# 18500_pack_v2.net
KiCad netlist of a schematic drawn in EAGLE
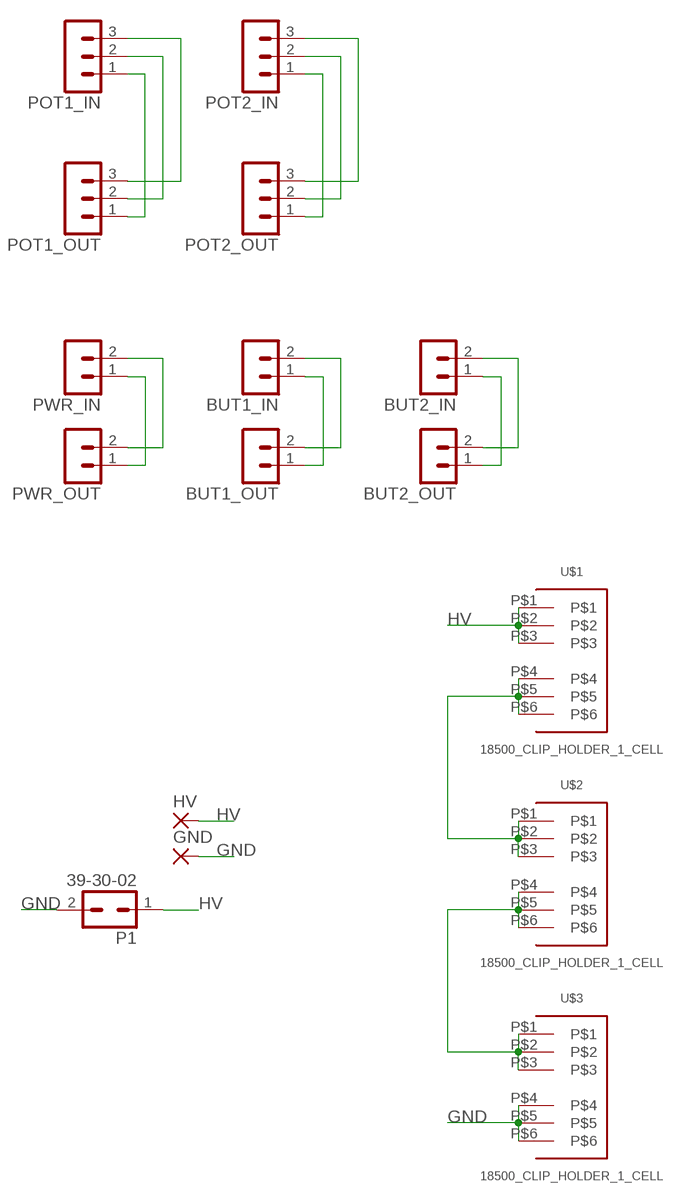
[diagram p0: schematic, sheet 1]

(export (version "E")
  (design (tool "Eeschema 10.0.6"))
  (components
    (comp (ref "BUT1_IN")
      (value "B2B-PH-K")
      (footprint "eagle-import:B2B-PH-K")
      (libsource (lib "eagle-import") (part "B2B-PH-K"))
    )
    (comp (ref "BUT1_OUT")
      (value "B2B-PH-K")
      (footprint "eagle-import:B2B-PH-K")
      (libsource (lib "eagle-import") (part "B2B-PH-K"))
    )
    (comp (ref "BUT2_IN")
      (value "B2B-PH-K")
      (footprint "eagle-import:B2B-PH-K")
      (libsource (lib "eagle-import") (part "B2B-PH-K"))
    )
    (comp (ref "BUT2_OUT")
      (value "B2B-PH-K")
      (footprint "eagle-import:B2B-PH-K")
      (libsource (lib "eagle-import") (part "B2B-PH-K"))
    )
    (comp (ref "GND")
      (value "2,54/1,1")
      (footprint "eagle-import:2,54_1,1")
      (libsource (lib "eagle-import") (part "2,54/1,1"))
    )
    (comp (ref "HV")
      (value "2,54/1,1")
      (footprint "eagle-import:2,54_1,1")
      (libsource (lib "eagle-import") (part "2,54/1,1"))
    )
    (comp (ref "P1")
      (value "39-30-02")
      (footprint "eagle-import:39-30-_02_")
      (libsource (lib "eagle-import") (part "39-30-?02?"))
    )
    (comp (ref "POT1_IN")
      (value "B3B-PH-K")
      (footprint "eagle-import:B3B-PH-K")
      (libsource (lib "eagle-import") (part "B3B-PH-K"))
    )
    (comp (ref "POT1_OUT")
      (value "B3B-PH-K")
      (footprint "eagle-import:B3B-PH-K")
      (libsource (lib "eagle-import") (part "B3B-PH-K"))
    )
    (comp (ref "POT2_IN")
      (value "B3B-PH-K")
      (footprint "eagle-import:B3B-PH-K")
      (libsource (lib "eagle-import") (part "B3B-PH-K"))
    )
    (comp (ref "POT2_OUT")
      (value "B3B-PH-K")
      (footprint "eagle-import:B3B-PH-K")
      (libsource (lib "eagle-import") (part "B3B-PH-K"))
    )
    (comp (ref "PWR_IN")
      (value "B2B-PH-K")
      (footprint "eagle-import:B2B-PH-K")
      (libsource (lib "eagle-import") (part "B2B-PH-K"))
    )
    (comp (ref "PWR_OUT")
      (value "B2B-PH-K")
      (footprint "eagle-import:B2B-PH-K")
      (libsource (lib "eagle-import") (part "B2B-PH-K"))
    )
    (comp (ref "U$1")
      (value "18500_CLIP_HOLDER_1_CELL")
      (footprint "eagle-import:3PINBATTERY_CLIP_1_CELL_18500")
      (libsource (lib "eagle-import") (part "18500_CLIP_HOLDER_1_CELL"))
    )
    (comp (ref "U$2")
      (value "18500_CLIP_HOLDER_1_CELL")
      (footprint "eagle-import:3PINBATTERY_CLIP_1_CELL_18500")
      (libsource (lib "eagle-import") (part "18500_CLIP_HOLDER_1_CELL"))
    )
    (comp (ref "U$3")
      (value "18500_CLIP_HOLDER_1_CELL")
      (footprint "eagle-import:3PINBATTERY_CLIP_1_CELL_18500")
      (libsource (lib "eagle-import") (part "18500_CLIP_HOLDER_1_CELL"))
    )
  )
  (nets
    (net (code "1") (name "/GND") (class "Default")
      (node (ref "GND") (pin "1") (pinfunction "P_1") (pintype "passive"))
      (node (ref "P1") (pin "2") (pinfunction "2_2") (pintype "passive"))
      (node (ref "U$3") (pin "P$4") (pinfunction "P$4_P$4") (pintype "bidirectional"))
      (node (ref "U$3") (pin "P$5") (pinfunction "P$5_P$5") (pintype "bidirectional"))
      (node (ref "U$3") (pin "P$6") (pinfunction "P$6_P$6") (pintype "bidirectional"))
    )
    (net (code "2") (name "/HV") (class "Default")
      (node (ref "HV") (pin "1") (pinfunction "P_1") (pintype "passive"))
      (node (ref "P1") (pin "1") (pinfunction "1_1") (pintype "passive"))
      (node (ref "U$1") (pin "P$1") (pinfunction "P$1_P$1") (pintype "bidirectional"))
      (node (ref "U$1") (pin "P$2") (pinfunction "P$2_P$2") (pintype "bidirectional"))
      (node (ref "U$1") (pin "P$3") (pinfunction "P$3_P$3") (pintype "bidirectional"))
    )
    (net (code "3") (name "Net-(BUT1_IN-Pad1)") (class "Default")
      (node (ref "BUT1_IN") (pin "1") (pinfunction "1_1") (pintype "passive"))
      (node (ref "BUT1_OUT") (pin "1") (pinfunction "1_1") (pintype "passive"))
    )
    (net (code "4") (name "Net-(BUT1_IN-Pad2)") (class "Default")
      (node (ref "BUT1_IN") (pin "2") (pinfunction "2_2") (pintype "passive"))
      (node (ref "BUT1_OUT") (pin "2") (pinfunction "2_2") (pintype "passive"))
    )
    (net (code "5") (name "Net-(BUT2_IN-Pad1)") (class "Default")
      (node (ref "BUT2_IN") (pin "1") (pinfunction "1_1") (pintype "passive"))
      (node (ref "BUT2_OUT") (pin "1") (pinfunction "1_1") (pintype "passive"))
    )
    (net (code "6") (name "Net-(BUT2_IN-Pad2)") (class "Default")
      (node (ref "BUT2_IN") (pin "2") (pinfunction "2_2") (pintype "passive"))
      (node (ref "BUT2_OUT") (pin "2") (pinfunction "2_2") (pintype "passive"))
    )
    (net (code "7") (name "Net-(POT1_IN-Pad1)") (class "Default")
      (node (ref "POT1_IN") (pin "1") (pinfunction "1_1") (pintype "passive"))
      (node (ref "POT1_OUT") (pin "1") (pinfunction "1_1") (pintype "passive"))
    )
    (net (code "8") (name "Net-(POT1_IN-Pad2)") (class "Default")
      (node (ref "POT1_IN") (pin "2") (pinfunction "2_2") (pintype "passive"))
      (node (ref "POT1_OUT") (pin "2") (pinfunction "2_2") (pintype "passive"))
    )
    (net (code "9") (name "Net-(POT1_IN-Pad3)") (class "Default")
      (node (ref "POT1_IN") (pin "3") (pinfunction "3_3") (pintype "passive"))
      (node (ref "POT1_OUT") (pin "3") (pinfunction "3_3") (pintype "passive"))
    )
    (net (code "10") (name "Net-(POT2_IN-Pad1)") (class "Default")
      (node (ref "POT2_IN") (pin "1") (pinfunction "1_1") (pintype "passive"))
      (node (ref "POT2_OUT") (pin "1") (pinfunction "1_1") (pintype "passive"))
    )
    (net (code "11") (name "Net-(POT2_IN-Pad2)") (class "Default")
      (node (ref "POT2_IN") (pin "2") (pinfunction "2_2") (pintype "passive"))
      (node (ref "POT2_OUT") (pin "2") (pinfunction "2_2") (pintype "passive"))
    )
    (net (code "12") (name "Net-(POT2_IN-Pad3)") (class "Default")
      (node (ref "POT2_IN") (pin "3") (pinfunction "3_3") (pintype "passive"))
      (node (ref "POT2_OUT") (pin "3") (pinfunction "3_3") (pintype "passive"))
    )
    (net (code "13") (name "Net-(PWR_IN-Pad1)") (class "Default")
      (node (ref "PWR_IN") (pin "1") (pinfunction "1_1") (pintype "passive"))
      (node (ref "PWR_OUT") (pin "1") (pinfunction "1_1") (pintype "passive"))
    )
    (net (code "14") (name "Net-(PWR_IN-Pad2)") (class "Default")
      (node (ref "PWR_IN") (pin "2") (pinfunction "2_2") (pintype "passive"))
      (node (ref "PWR_OUT") (pin "2") (pinfunction "2_2") (pintype "passive"))
    )
    (net (code "15") (name "Net-(U$1-PadP$4)") (class "Default")
      (node (ref "U$1") (pin "P$4") (pinfunction "P$4_P$4") (pintype "bidirectional"))
      (node (ref "U$1") (pin "P$5") (pinfunction "P$5_P$5") (pintype "bidirectional"))
      (node (ref "U$1") (pin "P$6") (pinfunction "P$6_P$6") (pintype "bidirectional"))
      (node (ref "U$2") (pin "P$1") (pinfunction "P$1_P$1") (pintype "bidirectional"))
      (node (ref "U$2") (pin "P$2") (pinfunction "P$2_P$2") (pintype "bidirectional"))
      (node (ref "U$2") (pin "P$3") (pinfunction "P$3_P$3") (pintype "bidirectional"))
    )
    (net (code "16") (name "Net-(U$2-PadP$4)") (class "Default")
      (node (ref "U$2") (pin "P$4") (pinfunction "P$4_P$4") (pintype "bidirectional"))
      (node (ref "U$2") (pin "P$5") (pinfunction "P$5_P$5") (pintype "bidirectional"))
      (node (ref "U$2") (pin "P$6") (pinfunction "P$6_P$6") (pintype "bidirectional"))
      (node (ref "U$3") (pin "P$1") (pinfunction "P$1_P$1") (pintype "bidirectional"))
      (node (ref "U$3") (pin "P$2") (pinfunction "P$2_P$2") (pintype "bidirectional"))
      (node (ref "U$3") (pin "P$3") (pinfunction "P$3_P$3") (pintype "bidirectional"))
    )
  )
)
